# ADCTest1.net
KiCad netlist of a schematic drawn in EAGLE
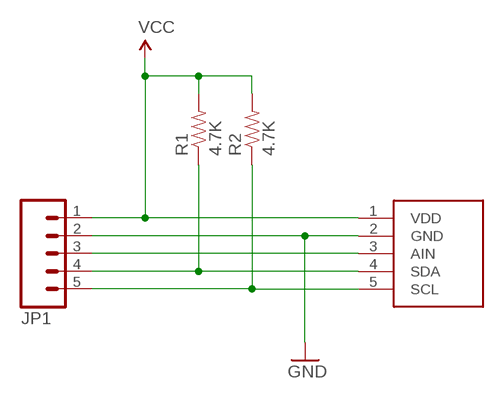
[diagram p0: schematic, sheet 1]

(export (version "E")
  (design (tool "Eeschema 10.0.6"))
  (components
    (comp (ref "JP1")
      (value "M05PTH")
      (footprint "eagle-import:1X05")
      (libsource (lib "eagle-import") (part "M05PTH"))
    )
    (comp (ref "R1")
      (value "4.7K")
      (footprint "eagle-import:0603-RES")
      (libsource (lib "eagle-import") (part "RES-4.7K-0603"))
    )
    (comp (ref "R2")
      (value "4.7K")
      (footprint "eagle-import:0603-RES")
      (libsource (lib "eagle-import") (part "RES-4.7K-0603"))
    )
    (comp (ref "U$1")
      (value "MCP3021-ADC")
      (footprint "eagle-import:SOT-23-5-MICROCHIP")
      (libsource (lib "eagle-import") (part "MCP3021-ADC"))
    )
  )
  (nets
    (net (code "1") (name "GND") (class "Default")
      (node (ref "JP1") (pin "2") (pinfunction "2_2") (pintype "passive"))
      (node (ref "U$1") (pin "2") (pinfunction "GND_2") (pintype "power_in"))
    )
    (net (code "2") (name "Net-(U$1-AIN)") (class "Default")
      (node (ref "JP1") (pin "3") (pinfunction "3_3") (pintype "passive"))
      (node (ref "U$1") (pin "3") (pinfunction "AIN_3") (pintype "input"))
    )
    (net (code "3") (name "Net-(U$1-SCL)") (class "Default")
      (node (ref "JP1") (pin "5") (pinfunction "5_5") (pintype "passive"))
      (node (ref "R2") (pin "1") (pinfunction "1_1") (pintype "passive"))
      (node (ref "U$1") (pin "5") (pinfunction "SCL_5") (pintype "bidirectional"))
    )
    (net (code "4") (name "Net-(U$1-SDA)") (class "Default")
      (node (ref "JP1") (pin "4") (pinfunction "4_4") (pintype "passive"))
      (node (ref "R1") (pin "1") (pinfunction "1_1") (pintype "passive"))
      (node (ref "U$1") (pin "4") (pinfunction "SDA_4") (pintype "bidirectional"))
    )
    (net (code "5") (name "VCC") (class "Default")
      (node (ref "JP1") (pin "1") (pinfunction "1_1") (pintype "passive"))
      (node (ref "R1") (pin "2") (pinfunction "2_2") (pintype "passive"))
      (node (ref "R2") (pin "2") (pinfunction "2_2") (pintype "passive"))
      (node (ref "U$1") (pin "1") (pinfunction "VDD_1") (pintype "power_in"))
    )
  )
)
